# 206eBreakout.net
KiCad netlist of a schematic drawn in EAGLE
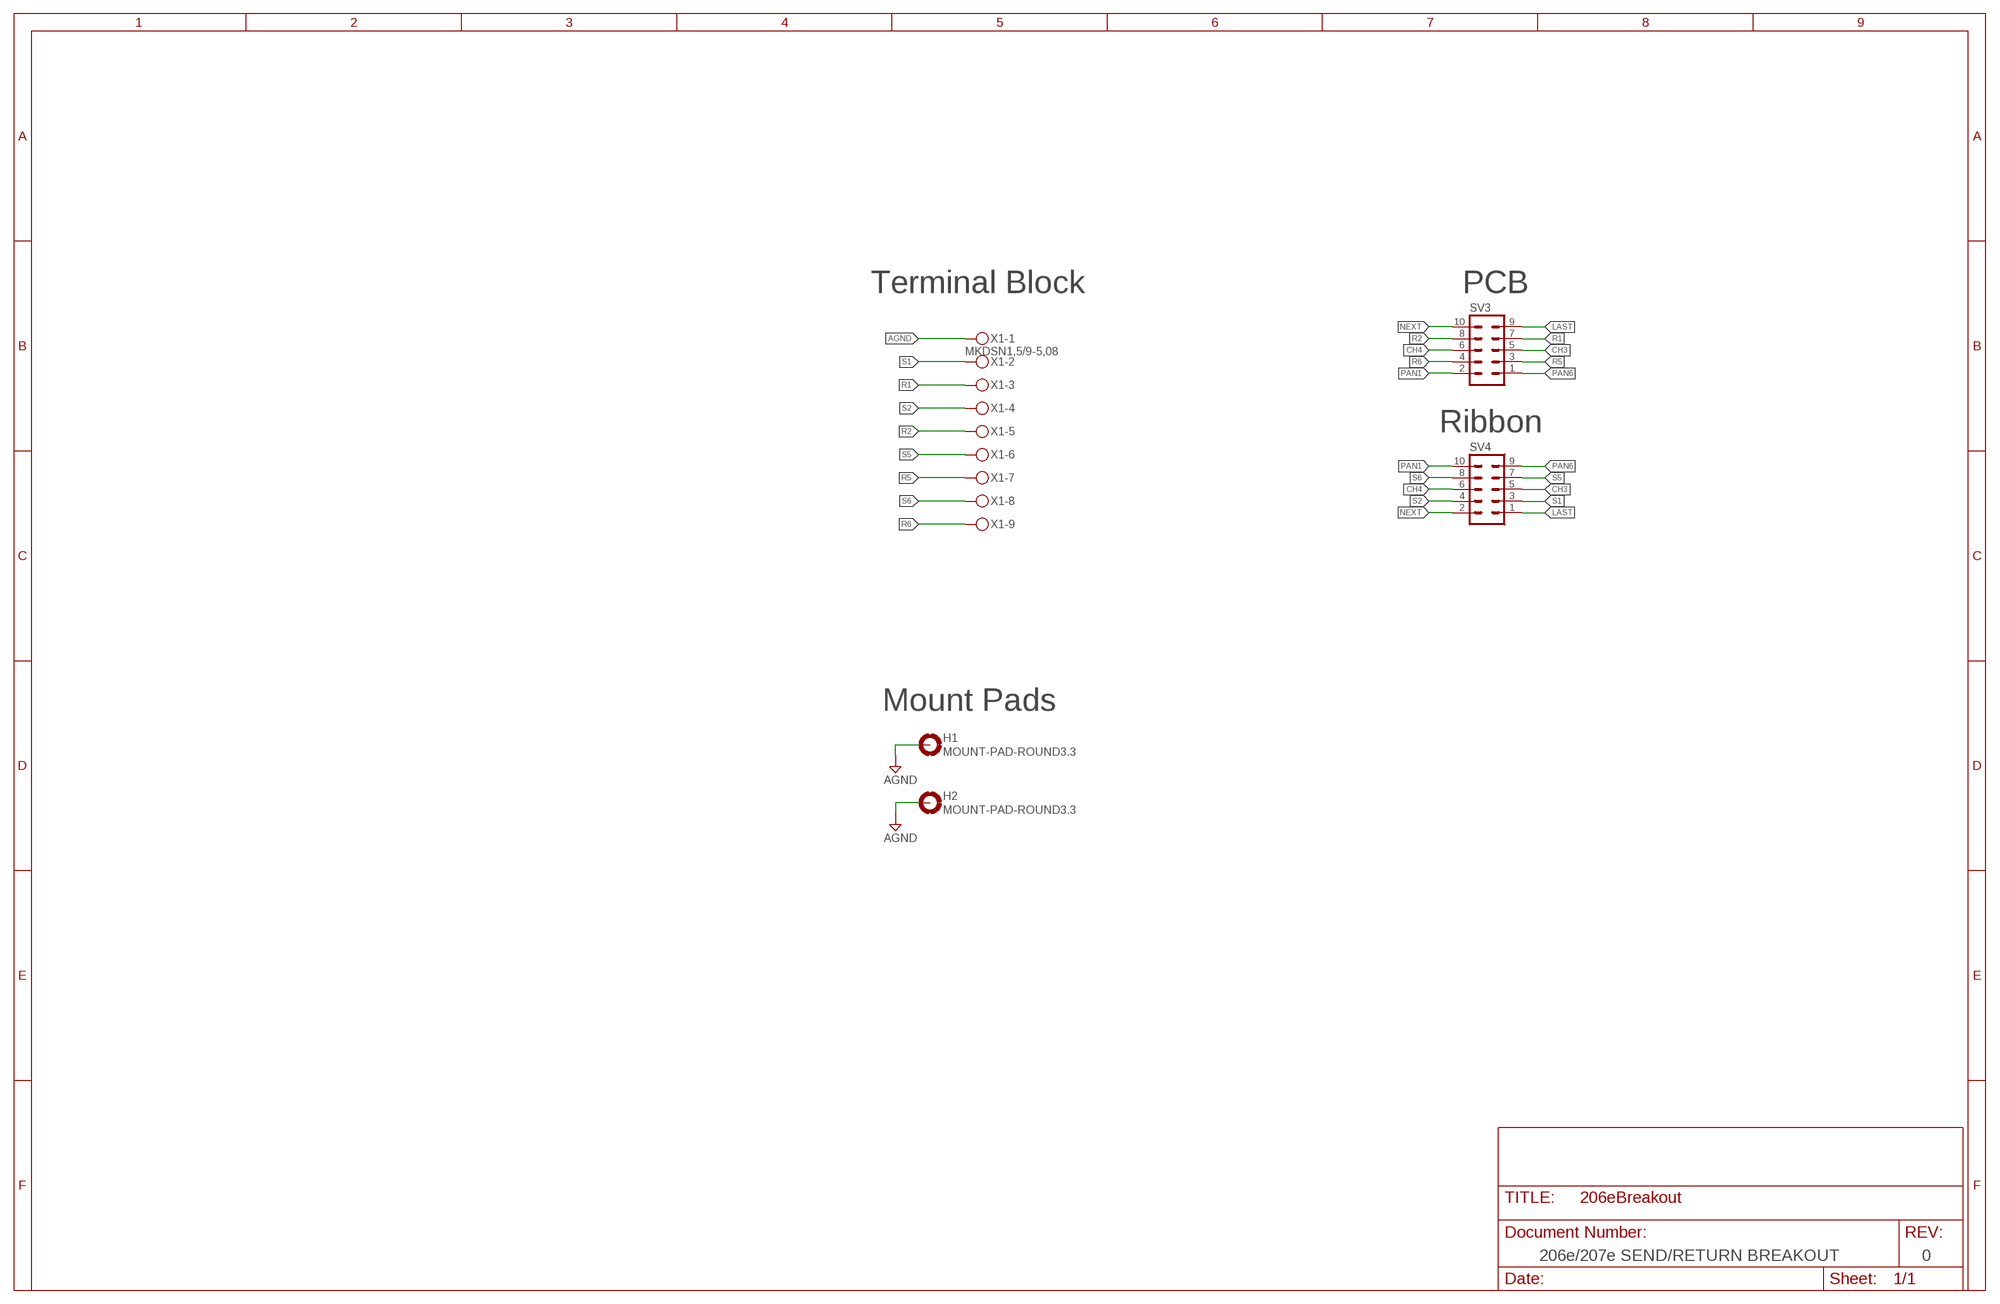
[diagram p0: schematic, sheet 1]

(export (version "E")
  (design (tool "Eeschema 10.0.6"))
  (components
    (comp (ref "H1")
      (value "MOUNT-PAD-ROUND3.3")
      (footprint "eagle-import:3,3-PAD")
      (libsource (lib "eagle-import") (part "MOUNT-PAD-ROUND3.3"))
    )
    (comp (ref "H2")
      (value "MOUNT-PAD-ROUND3.3")
      (footprint "eagle-import:3,3-PAD")
      (libsource (lib "eagle-import") (part "MOUNT-PAD-ROUND3.3"))
    )
    (comp (ref "SV3")
      (value "MA05-2")
      (footprint "eagle-import:MA05-2")
      (fields (field (name "MF") "TE CONNECTIVITY") (field (name "MPN") "4-146251-0"))
      (libsource (lib "eagle-import") (part "MA05-2"))
    )
    (comp (ref "SV4")
      (value "MA05-2")
      (footprint "eagle-import:MA05-2")
      (fields (field (name "MF") "TE CONNECTIVITY") (field (name "MPN") "4-146251-0"))
      (libsource (lib "eagle-import") (part "MA05-2"))
    )
    (comp (ref "X1")
      (value "MKDSN1,5/9-5,08")
      (footprint "eagle-import:MKDSN1,5_9-5,08")
      (libsource (lib "eagle-import") (part "MKDSN1,5/9-5,08"))
    )
  )
  (nets
    (net (code "1") (name "AGND") (class "Default")
      (node (ref "H1") (pin "B3,3") (pinfunction "MOUNT_B3,3") (pintype "passive"))
      (node (ref "H2") (pin "B3,3") (pinfunction "MOUNT_B3,3") (pintype "passive"))
      (node (ref "X1") (pin "1") (pinfunction "KL_1") (pintype "passive"))
    )
    (net (code "2") (name "CH3") (class "Default")
      (node (ref "SV3") (pin "5") (pinfunction "5_5") (pintype "passive"))
      (node (ref "SV4") (pin "5") (pinfunction "5_5") (pintype "passive"))
    )
    (net (code "3") (name "CH4") (class "Default")
      (node (ref "SV3") (pin "6") (pinfunction "6_6") (pintype "passive"))
      (node (ref "SV4") (pin "6") (pinfunction "6_6") (pintype "passive"))
    )
    (net (code "4") (name "LAST") (class "Default")
      (node (ref "SV3") (pin "9") (pinfunction "9_9") (pintype "passive"))
      (node (ref "SV4") (pin "1") (pinfunction "1_1") (pintype "passive"))
    )
    (net (code "5") (name "NEXT") (class "Default")
      (node (ref "SV3") (pin "10") (pinfunction "10_10") (pintype "passive"))
      (node (ref "SV4") (pin "2") (pinfunction "2_2") (pintype "passive"))
    )
    (net (code "6") (name "PAN1") (class "Default")
      (node (ref "SV3") (pin "2") (pinfunction "2_2") (pintype "passive"))
      (node (ref "SV4") (pin "10") (pinfunction "10_10") (pintype "passive"))
    )
    (net (code "7") (name "PAN6") (class "Default")
      (node (ref "SV3") (pin "1") (pinfunction "1_1") (pintype "passive"))
      (node (ref "SV4") (pin "9") (pinfunction "9_9") (pintype "passive"))
    )
    (net (code "8") (name "R1") (class "Default")
      (node (ref "SV3") (pin "7") (pinfunction "7_7") (pintype "passive"))
      (node (ref "X1") (pin "3") (pinfunction "KL_3") (pintype "passive"))
    )
    (net (code "9") (name "R2") (class "Default")
      (node (ref "SV3") (pin "8") (pinfunction "8_8") (pintype "passive"))
      (node (ref "X1") (pin "5") (pinfunction "KL_5") (pintype "passive"))
    )
    (net (code "10") (name "R5") (class "Default")
      (node (ref "SV3") (pin "3") (pinfunction "3_3") (pintype "passive"))
      (node (ref "X1") (pin "7") (pinfunction "KL_7") (pintype "passive"))
    )
    (net (code "11") (name "R6") (class "Default")
      (node (ref "SV3") (pin "4") (pinfunction "4_4") (pintype "passive"))
      (node (ref "X1") (pin "9") (pinfunction "KL_9") (pintype "passive"))
    )
    (net (code "12") (name "S1") (class "Default")
      (node (ref "SV4") (pin "3") (pinfunction "3_3") (pintype "passive"))
      (node (ref "X1") (pin "2") (pinfunction "KL_2") (pintype "passive"))
    )
    (net (code "13") (name "S2") (class "Default")
      (node (ref "SV4") (pin "4") (pinfunction "4_4") (pintype "passive"))
      (node (ref "X1") (pin "4") (pinfunction "KL_4") (pintype "passive"))
    )
    (net (code "14") (name "S5") (class "Default")
      (node (ref "SV4") (pin "7") (pinfunction "7_7") (pintype "passive"))
      (node (ref "X1") (pin "6") (pinfunction "KL_6") (pintype "passive"))
    )
    (net (code "15") (name "S6") (class "Default")
      (node (ref "SV4") (pin "8") (pinfunction "8_8") (pintype "passive"))
      (node (ref "X1") (pin "8") (pinfunction "KL_8") (pintype "passive"))
    )
  )
)
